# Potentiostat.net
KiCad netlist of a schematic drawn in EAGLE
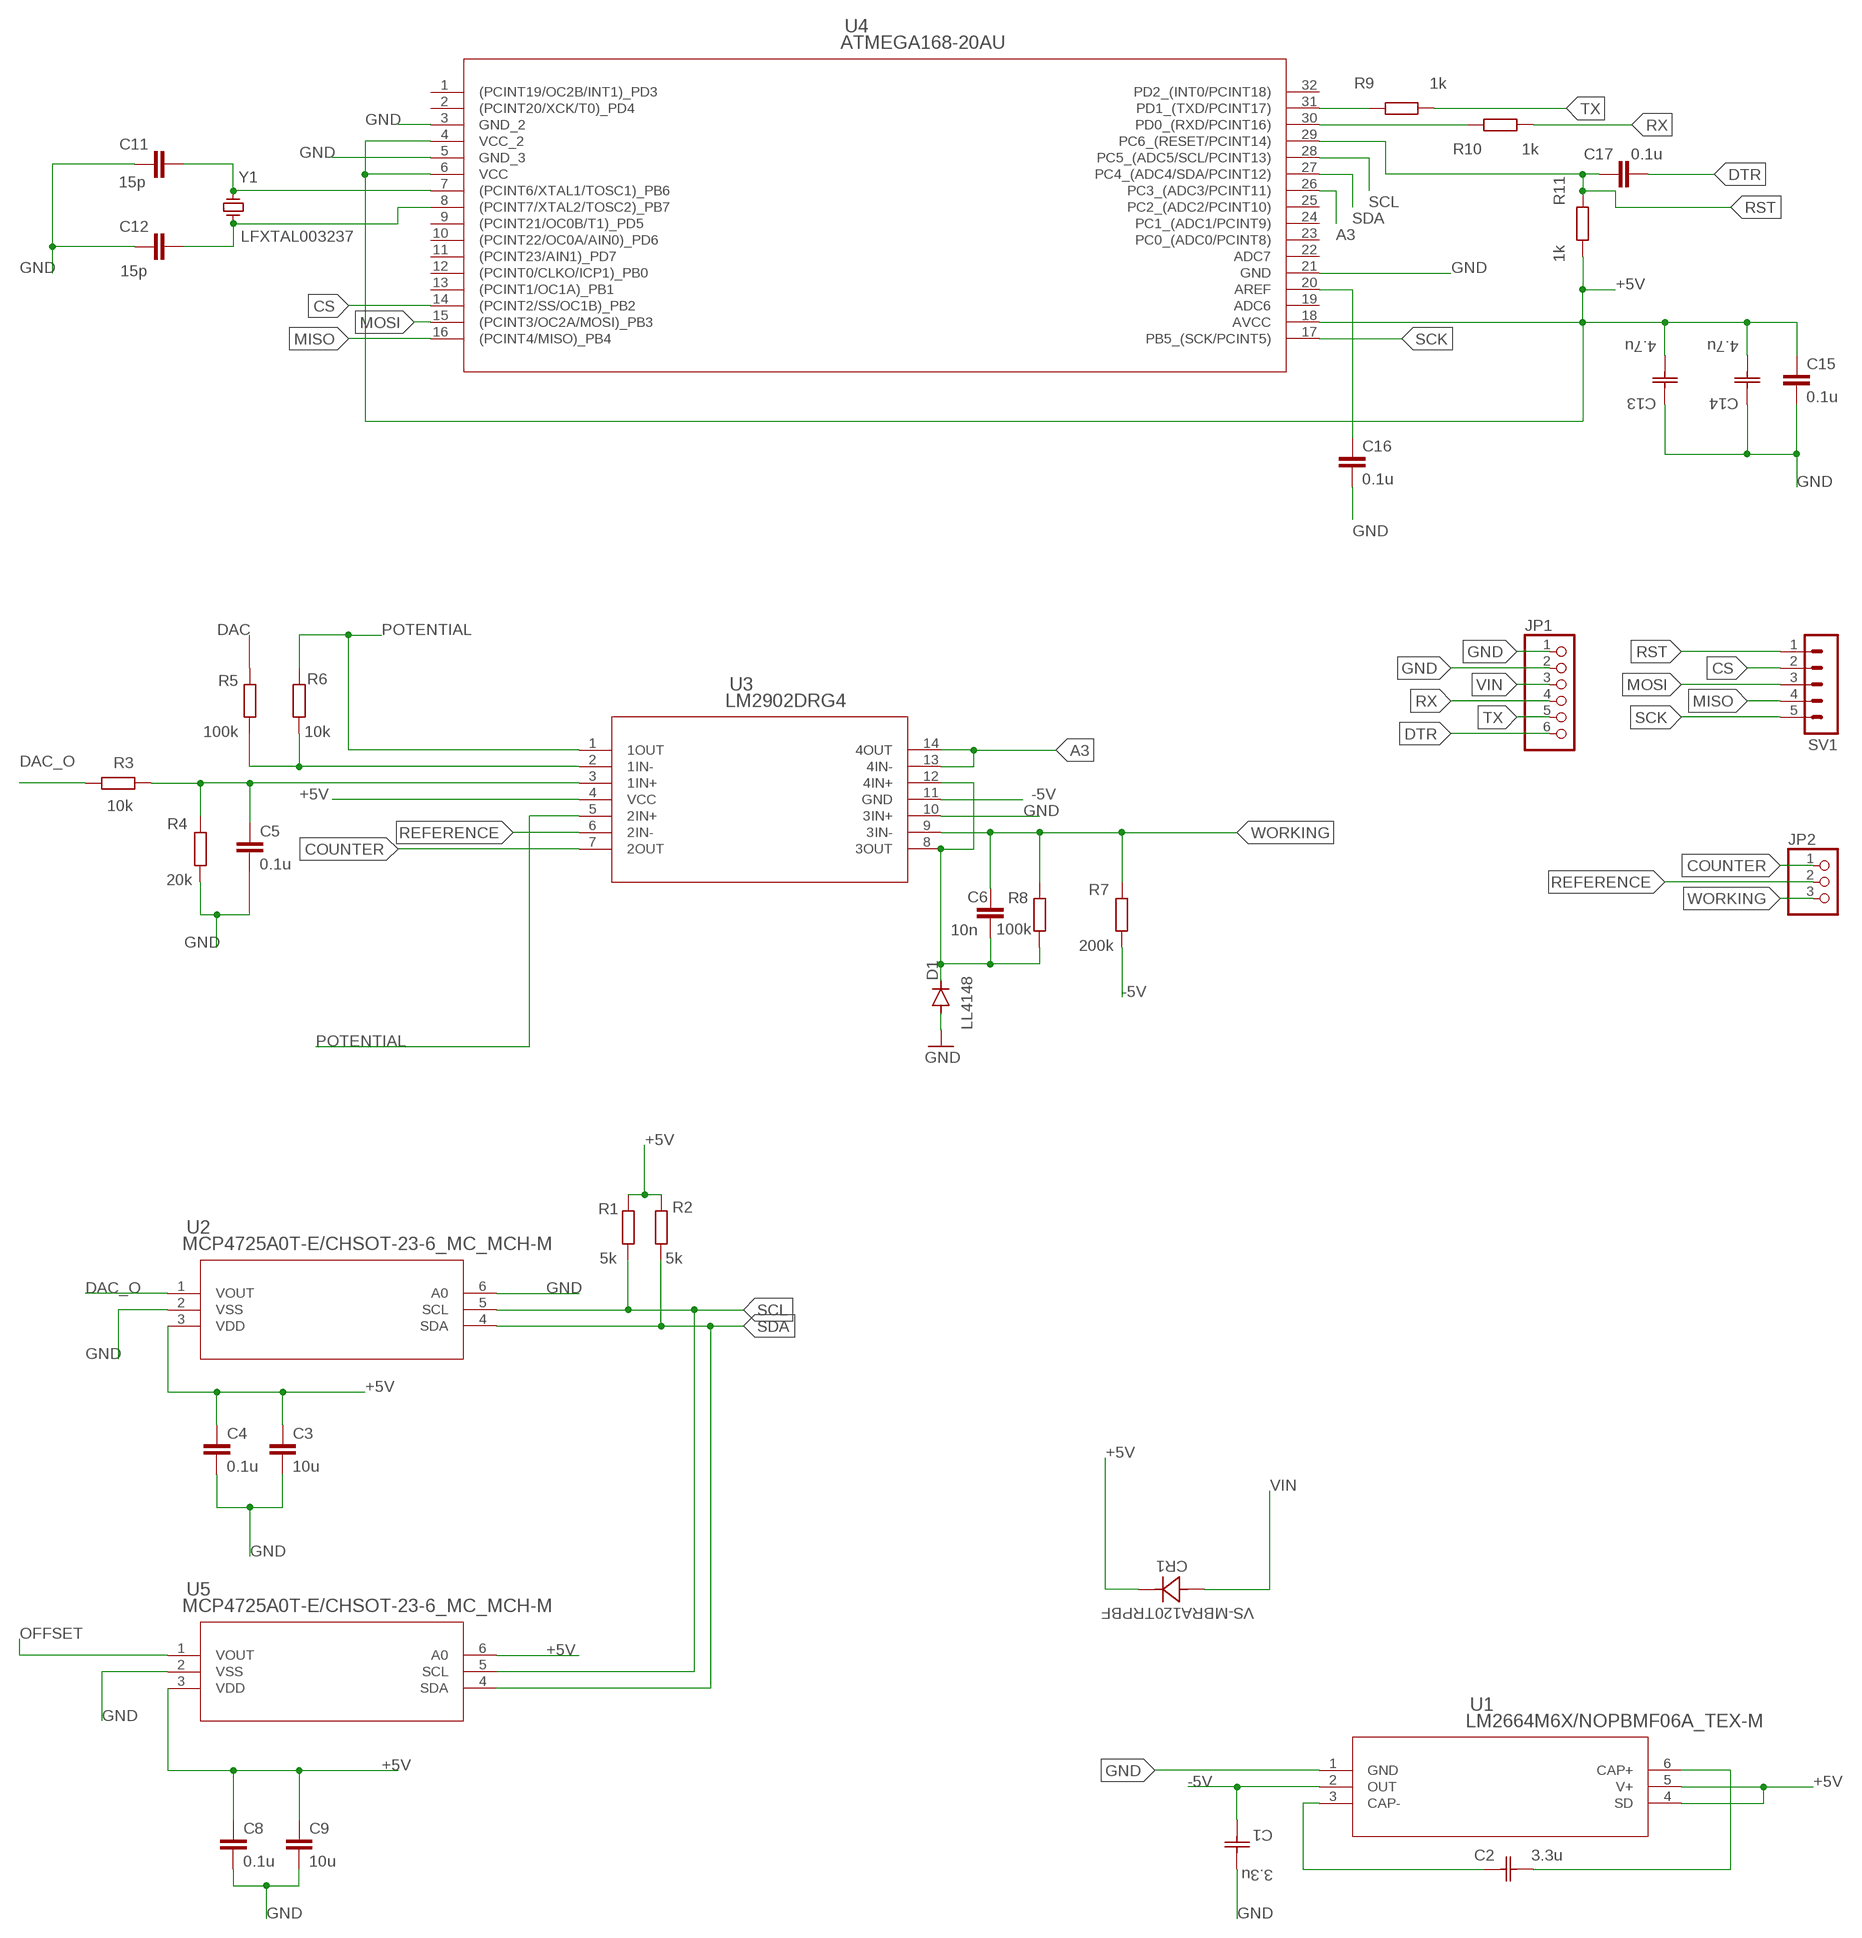
[diagram p0: schematic, sheet 1]

(export (version "E")
  (design (tool "Eeschema 10.0.6"))
  (components
    (comp (ref "C1")
      (value "3.3u")
      (footprint "eagle-import:CAP_293D_A_VIS-M")
      (fields (field (name "MANUFACTURER_PART_NUMBER") "293D335X9016A2TE3"))
      (libsource (lib "eagle-import") (part "293D335X9016A2TE3CAP_293D_A_VIS-M"))
    )
    (comp (ref "C2")
      (value "3.3u")
      (footprint "eagle-import:CAP_293D_A_VIS-M")
      (fields (field (name "MANUFACTURER_PART_NUMBER") "293D335X9016A2TE3"))
      (libsource (lib "eagle-import") (part "293D335X9016A2TE3CAP_293D_A_VIS-M"))
    )
    (comp (ref "C3")
      (value "10u")
      (footprint "eagle-import:C0805")
      (libsource (lib "eagle-import") (part "C-EUC0805"))
    )
    (comp (ref "C4")
      (value "0.1u")
      (footprint "eagle-import:C0805")
      (libsource (lib "eagle-import") (part "C-EUC0805"))
    )
    (comp (ref "C5")
      (value "0.1u")
      (footprint "eagle-import:C0805")
      (libsource (lib "eagle-import") (part "C-EUC0805"))
    )
    (comp (ref "C6")
      (value "10n")
      (footprint "eagle-import:C0805")
      (libsource (lib "eagle-import") (part "C-EUC0805"))
    )
    (comp (ref "C8")
      (value "0.1u")
      (footprint "eagle-import:C0805")
      (libsource (lib "eagle-import") (part "C-EUC0805"))
    )
    (comp (ref "C9")
      (value "10u")
      (footprint "eagle-import:C0805")
      (libsource (lib "eagle-import") (part "C-EUC0805"))
    )
    (comp (ref "C11")
      (value "15p")
      (footprint "eagle-import:C0805")
      (libsource (lib "eagle-import") (part "C-EUC0805"))
    )
    (comp (ref "C12")
      (value "15p")
      (footprint "eagle-import:C0805")
      (libsource (lib "eagle-import") (part "C-EUC0805"))
    )
    (comp (ref "C13")
      (value "4.7u")
      (footprint "eagle-import:CAP_293D_A_VIS-M")
      (fields (field (name "MANUFACTURER_PART_NUMBER") "293D335X9016A2TE3"))
      (libsource (lib "eagle-import") (part "293D335X9016A2TE3CAP_293D_A_VIS-M"))
    )
    (comp (ref "C14")
      (value "4.7u")
      (footprint "eagle-import:CAP_293D_A_VIS-M")
      (fields (field (name "MANUFACTURER_PART_NUMBER") "293D335X9016A2TE3"))
      (libsource (lib "eagle-import") (part "293D335X9016A2TE3CAP_293D_A_VIS-M"))
    )
    (comp (ref "C15")
      (value "0.1u")
      (footprint "eagle-import:C0805")
      (libsource (lib "eagle-import") (part "C-EUC0805"))
    )
    (comp (ref "C16")
      (value "0.1u")
      (footprint "eagle-import:C0805")
      (libsource (lib "eagle-import") (part "C-EUC0805"))
    )
    (comp (ref "C17")
      (value "0.1u")
      (footprint "eagle-import:C0805")
      (libsource (lib "eagle-import") (part "C-EUC0805"))
    )
    (comp (ref "CR1")
      (value "VS-MBRA120TRPBF")
      (footprint "eagle-import:DIODE_SMA_VIS")
      (libsource (lib "eagle-import") (part "VS-MBRA120TRPBF"))
    )
    (comp (ref "D1")
      (value "LL4148")
      (footprint "eagle-import:SOD80C")
      (libsource (lib "eagle-import") (part "DIODE-SOD80C"))
    )
    (comp (ref "JP1")
      (value "PINHD-1X6CB")
      (footprint "eagle-import:1X06-CLEANBIG")
      (libsource (lib "eagle-import") (part "PINHD-1X6CB"))
    )
    (comp (ref "JP2")
      (value "PINHD-1X3CB")
      (footprint "eagle-import:1X03-CLEANBIG")
      (libsource (lib "eagle-import") (part "PINHD-1X3CB"))
    )
    (comp (ref "R1")
      (value "5k")
      (footprint "eagle-import:R0805")
      (libsource (lib "eagle-import") (part "R-EU_R0805"))
    )
    (comp (ref "R2")
      (value "5k")
      (footprint "eagle-import:R0805")
      (libsource (lib "eagle-import") (part "R-EU_R0805"))
    )
    (comp (ref "R3")
      (value "10k")
      (footprint "eagle-import:R0805")
      (libsource (lib "eagle-import") (part "R-EU_R0805"))
    )
    (comp (ref "R4")
      (value "20k")
      (footprint "eagle-import:R0805")
      (libsource (lib "eagle-import") (part "R-EU_R0805"))
    )
    (comp (ref "R5")
      (value "100k")
      (footprint "eagle-import:R0805")
      (libsource (lib "eagle-import") (part "R-EU_R0805"))
    )
    (comp (ref "R6")
      (value "10k")
      (footprint "eagle-import:R0805")
      (libsource (lib "eagle-import") (part "R-EU_R0805"))
    )
    (comp (ref "R7")
      (value "200k")
      (footprint "eagle-import:R0805")
      (libsource (lib "eagle-import") (part "R-EU_R0805"))
    )
    (comp (ref "R8")
      (value "100k")
      (footprint "eagle-import:R0805")
      (libsource (lib "eagle-import") (part "R-EU_R0805"))
    )
    (comp (ref "R9")
      (value "1k")
      (footprint "eagle-import:R0805")
      (libsource (lib "eagle-import") (part "R-EU_R0805"))
    )
    (comp (ref "R10")
      (value "1k")
      (footprint "eagle-import:R0805")
      (libsource (lib "eagle-import") (part "R-EU_R0805"))
    )
    (comp (ref "R11")
      (value "1k")
      (footprint "eagle-import:R0805")
      (libsource (lib "eagle-import") (part "R-EU_R0805"))
    )
    (comp (ref "SV1")
      (value "MA05-1")
      (footprint "eagle-import:MA05-1")
      (libsource (lib "eagle-import") (part "MA05-1"))
    )
    (comp (ref "U1")
      (value "LM2664M6X/NOPBMF06A_TEX-M")
      (footprint "eagle-import:MF06A_TEX-M")
      (fields (field (name "MANUFACTURER_PART_NUMBER") "LM2664M6X/NOPB"))
      (libsource (lib "eagle-import") (part "LM2664M6X/NOPBMF06A_TEX-M"))
    )
    (comp (ref "U2")
      (value "MCP4725A0T-E/CHSOT-23-6_MC_MCH-M")
      (footprint "eagle-import:SOT-23-6_MC_MCH-M")
      (fields (field (name "MANUFACTURER_PART_NUMBER") "MCP4725A0T-E/CH"))
      (libsource (lib "eagle-import") (part "MCP4725A0T-E/CHSOT-23-6_MC_MCH-M"))
    )
    (comp (ref "U3")
      (value "LM2902DRG4")
      (footprint "eagle-import:D14_TEX")
      (fields (field (name "MANUFACTURER") "Texas Instruments"))
      (libsource (lib "eagle-import") (part "LM2902DRG4"))
    )
    (comp (ref "U4")
      (value "ATMEGA168-20AU")
      (footprint "eagle-import:32A_ATM")
      (fields (field (name "COPYRIGHT") "Copyright (C) 2015 Accelerated Designs. All rights reserved"))
      (libsource (lib "eagle-import") (part "ATMEGA168-20AU"))
    )
    (comp (ref "U5")
      (value "MCP4725A0T-E/CHSOT-23-6_MC_MCH-M")
      (footprint "eagle-import:SOT-23-6_MC_MCH-M")
      (fields (field (name "MANUFACTURER_PART_NUMBER") "MCP4725A0T-E/CH"))
      (libsource (lib "eagle-import") (part "MCP4725A0T-E/CHSOT-23-6_MC_MCH-M"))
    )
    (comp (ref "Y1")
      (value "LFXTAL003237")
      (footprint "eagle-import:XTAL1140X490X430N")
      (fields (field (name "MF") "IQD Frequency Products"))
      (libsource (lib "eagle-import") (part "LFXTAL003237"))
    )
  )
  (nets
    (net (code "1") (name "/+5V") (class "Default")
      (node (ref "C13") (pin "2") (pinfunction "2_2") (pintype "passive"))
      (node (ref "C14") (pin "2") (pinfunction "2_2") (pintype "passive"))
      (node (ref "C15") (pin "1") (pinfunction "1_1") (pintype "passive"))
      (node (ref "C3") (pin "1") (pinfunction "1_1") (pintype "passive"))
      (node (ref "C4") (pin "1") (pinfunction "1_1") (pintype "passive"))
      (node (ref "C8") (pin "1") (pinfunction "1_1") (pintype "passive"))
      (node (ref "C9") (pin "1") (pinfunction "1_1") (pintype "passive"))
      (node (ref "CR1") (pin "1") (pinfunction "1_1") (pintype "passive"))
      (node (ref "R1") (pin "2") (pinfunction "2_2") (pintype "passive"))
      (node (ref "R11") (pin "1") (pinfunction "1_1") (pintype "passive"))
      (node (ref "R2") (pin "2") (pinfunction "2_2") (pintype "passive"))
      (node (ref "U1") (pin "4") (pinfunction "SD_4") (pintype "passive"))
      (node (ref "U1") (pin "5") (pinfunction "V+_5") (pintype "input"))
      (node (ref "U2") (pin "3") (pinfunction "VDD_3") (pintype "passive"))
      (node (ref "U3") (pin "4") (pinfunction "VCC_4") (pintype "power_in"))
      (node (ref "U4") (pin "18") (pinfunction "AVCC_18") (pintype "power_in"))
      (node (ref "U4") (pin "4") (pinfunction "VCC_2_4") (pintype "power_in"))
      (node (ref "U4") (pin "6") (pinfunction "VCC_6") (pintype "power_in"))
      (node (ref "U5") (pin "3") (pinfunction "VDD_3") (pintype "passive"))
      (node (ref "U5") (pin "6") (pinfunction "A0_6") (pintype "passive"))
    )
    (net (code "2") (name "/-5V") (class "Default")
      (node (ref "C1") (pin "2") (pinfunction "2_2") (pintype "passive"))
      (node (ref "R7") (pin "1") (pinfunction "1_1") (pintype "passive"))
      (node (ref "U1") (pin "2") (pinfunction "OUT_2") (pintype "output"))
      (node (ref "U3") (pin "11") (pinfunction "GND_11") (pintype "power_in"))
    )
    (net (code "3") (name "/DAC") (class "Default")
      (node (ref "R5") (pin "2") (pinfunction "2_2") (pintype "passive"))
    )
    (net (code "4") (name "/DAC_O") (class "Default")
      (node (ref "R3") (pin "2") (pinfunction "2_2") (pintype "passive"))
      (node (ref "U2") (pin "1") (pinfunction "VOUT_1") (pintype "passive"))
    )
    (net (code "5") (name "/OFFSET") (class "Default")
      (node (ref "U5") (pin "1") (pinfunction "VOUT_1") (pintype "passive"))
    )
    (net (code "6") (name "/POTENTIAL") (class "Default")
      (node (ref "R6") (pin "2") (pinfunction "2_2") (pintype "passive"))
      (node (ref "U3") (pin "1") (pinfunction "1OUT_1") (pintype "output"))
      (node (ref "U3") (pin "5") (pinfunction "2IN+_5") (pintype "input"))
    )
    (net (code "7") (name "A3") (class "Default")
      (node (ref "U3") (pin "13") (pinfunction "4IN-_13") (pintype "input"))
      (node (ref "U3") (pin "14") (pinfunction "4OUT_14") (pintype "output"))
      (node (ref "U4") (pin "26") (pinfunction "PC3_(ADC3/PCINT11)_26") (pintype "bidirectional"))
    )
    (net (code "8") (name "COUNTER") (class "Default")
      (node (ref "JP2") (pin "1") (pinfunction "1_1") (pintype "passive"))
      (node (ref "U3") (pin "7") (pinfunction "2OUT_7") (pintype "output"))
    )
    (net (code "9") (name "CS") (class "Default")
      (node (ref "SV1") (pin "2") (pinfunction "2_2") (pintype "passive"))
      (node (ref "U4") (pin "14") (pinfunction "(PCINT2/SS/OC1B)_PB2_14") (pintype "bidirectional"))
    )
    (net (code "10") (name "DTR") (class "Default")
      (node (ref "C17") (pin "2") (pinfunction "2_2") (pintype "passive"))
      (node (ref "JP1") (pin "6") (pinfunction "6_6") (pintype "passive"))
    )
    (net (code "11") (name "GND") (class "Default")
      (node (ref "C1") (pin "1") (pinfunction "1_1") (pintype "passive"))
      (node (ref "C11") (pin "1") (pinfunction "1_1") (pintype "passive"))
      (node (ref "C12") (pin "1") (pinfunction "1_1") (pintype "passive"))
      (node (ref "C13") (pin "1") (pinfunction "1_1") (pintype "passive"))
      (node (ref "C14") (pin "1") (pinfunction "1_1") (pintype "passive"))
      (node (ref "C15") (pin "2") (pinfunction "2_2") (pintype "passive"))
      (node (ref "C16") (pin "2") (pinfunction "2_2") (pintype "passive"))
      (node (ref "C3") (pin "2") (pinfunction "2_2") (pintype "passive"))
      (node (ref "C4") (pin "2") (pinfunction "2_2") (pintype "passive"))
      (node (ref "C5") (pin "2") (pinfunction "2_2") (pintype "passive"))
      (node (ref "C8") (pin "2") (pinfunction "2_2") (pintype "passive"))
      (node (ref "C9") (pin "2") (pinfunction "2_2") (pintype "passive"))
      (node (ref "D1") (pin "A") (pinfunction "A_A") (pintype "passive"))
      (node (ref "JP1") (pin "1") (pinfunction "1_1") (pintype "passive"))
      (node (ref "JP1") (pin "2") (pinfunction "2_2") (pintype "passive"))
      (node (ref "R4") (pin "1") (pinfunction "1_1") (pintype "passive"))
      (node (ref "U1") (pin "1") (pinfunction "GND_1") (pintype "passive"))
      (node (ref "U2") (pin "2") (pinfunction "VSS_2") (pintype "passive"))
      (node (ref "U2") (pin "6") (pinfunction "A0_6") (pintype "passive"))
      (node (ref "U3") (pin "10") (pinfunction "3IN+_10") (pintype "input"))
      (node (ref "U4") (pin "21") (pinfunction "GND_21") (pintype "power_in"))
      (node (ref "U4") (pin "3") (pinfunction "GND_2_3") (pintype "power_in"))
      (node (ref "U4") (pin "5") (pinfunction "GND_3_5") (pintype "power_in"))
      (node (ref "U5") (pin "2") (pinfunction "VSS_2") (pintype "passive"))
    )
    (net (code "12") (name "MISO") (class "Default")
      (node (ref "SV1") (pin "4") (pinfunction "4_4") (pintype "passive"))
      (node (ref "U4") (pin "16") (pinfunction "(PCINT4/MISO)_PB4_16") (pintype "bidirectional"))
    )
    (net (code "13") (name "MOSI") (class "Default")
      (node (ref "SV1") (pin "3") (pinfunction "3_3") (pintype "passive"))
      (node (ref "U4") (pin "15") (pinfunction "(PCINT3/OC2A/MOSI)_PB3_15") (pintype "bidirectional"))
    )
    (net (code "14") (name "Net-(U1-CAP+)") (class "Default")
      (node (ref "C2") (pin "2") (pinfunction "2_2") (pintype "passive"))
      (node (ref "U1") (pin "6") (pinfunction "CAP+_6") (pintype "passive"))
    )
    (net (code "15") (name "Net-(U1-CAP-)") (class "Default")
      (node (ref "C2") (pin "1") (pinfunction "1_1") (pintype "passive"))
      (node (ref "U1") (pin "3") (pinfunction "CAP-_3") (pintype "passive"))
    )
    (net (code "16") (name "Net-(U3-1IN+)") (class "Default")
      (node (ref "C5") (pin "1") (pinfunction "1_1") (pintype "passive"))
      (node (ref "R3") (pin "1") (pinfunction "1_1") (pintype "passive"))
      (node (ref "R4") (pin "2") (pinfunction "2_2") (pintype "passive"))
      (node (ref "U3") (pin "3") (pinfunction "1IN+_3") (pintype "input"))
    )
    (net (code "17") (name "Net-(U3-1IN-)") (class "Default")
      (node (ref "R5") (pin "1") (pinfunction "1_1") (pintype "passive"))
      (node (ref "R6") (pin "1") (pinfunction "1_1") (pintype "passive"))
      (node (ref "U3") (pin "2") (pinfunction "1IN-_2") (pintype "input"))
    )
    (net (code "18") (name "Net-(U3-3OUT)") (class "Default")
      (node (ref "C6") (pin "2") (pinfunction "2_2") (pintype "passive"))
      (node (ref "D1") (pin "C") (pinfunction "C_C") (pintype "passive"))
      (node (ref "R8") (pin "1") (pinfunction "1_1") (pintype "passive"))
      (node (ref "U3") (pin "12") (pinfunction "4IN+_12") (pintype "input"))
      (node (ref "U3") (pin "8") (pinfunction "3OUT_8") (pintype "output"))
    )
    (net (code "19") (name "Net-(U4-(PCINT6{slash}XTAL1{slash}TOSC1)_PB6)") (class "Default")
      (node (ref "C11") (pin "2") (pinfunction "2_2") (pintype "passive"))
      (node (ref "U4") (pin "7") (pinfunction "(PCINT6/XTAL1/TOSC1)_PB6_7") (pintype "bidirectional"))
      (node (ref "Y1") (pin "2") (pinfunction "2_2") (pintype "passive"))
    )
    (net (code "20") (name "Net-(U4-(PCINT7{slash}XTAL2{slash}TOSC2)_PB7)") (class "Default")
      (node (ref "C12") (pin "2") (pinfunction "2_2") (pintype "passive"))
      (node (ref "U4") (pin "8") (pinfunction "(PCINT7/XTAL2/TOSC2)_PB7_8") (pintype "bidirectional"))
      (node (ref "Y1") (pin "1") (pinfunction "1_1") (pintype "passive"))
    )
    (net (code "21") (name "Net-(U4-AREF)") (class "Default")
      (node (ref "C16") (pin "1") (pinfunction "1_1") (pintype "passive"))
      (node (ref "U4") (pin "20") (pinfunction "AREF_20") (pintype "passive"))
    )
    (net (code "22") (name "Net-(U4-PD0_(RXD{slash}PCINT16))") (class "Default")
      (node (ref "R10") (pin "2") (pinfunction "2_2") (pintype "passive"))
      (node (ref "U4") (pin "30") (pinfunction "PD0_(RXD/PCINT16)_30") (pintype "bidirectional"))
    )
    (net (code "23") (name "Net-(U4-PD1_(TXD{slash}PCINT17))") (class "Default")
      (node (ref "R9") (pin "2") (pinfunction "2_2") (pintype "passive"))
      (node (ref "U4") (pin "31") (pinfunction "PD1_(TXD/PCINT17)_31") (pintype "bidirectional"))
    )
    (net (code "24") (name "REFERENCE") (class "Default")
      (node (ref "JP2") (pin "2") (pinfunction "2_2") (pintype "passive"))
      (node (ref "U3") (pin "6") (pinfunction "2IN-_6") (pintype "input"))
    )
    (net (code "25") (name "RST") (class "Default")
      (node (ref "C17") (pin "1") (pinfunction "1_1") (pintype "passive"))
      (node (ref "R11") (pin "2") (pinfunction "2_2") (pintype "passive"))
      (node (ref "SV1") (pin "1") (pinfunction "1_1") (pintype "passive"))
      (node (ref "U4") (pin "29") (pinfunction "PC6_(RESET/PCINT14)_29") (pintype "bidirectional"))
    )
    (net (code "26") (name "RX") (class "Default")
      (node (ref "JP1") (pin "4") (pinfunction "4_4") (pintype "passive"))
      (node (ref "R10") (pin "1") (pinfunction "1_1") (pintype "passive"))
    )
    (net (code "27") (name "SCK") (class "Default")
      (node (ref "SV1") (pin "5") (pinfunction "5_5") (pintype "passive"))
      (node (ref "U4") (pin "17") (pinfunction "PB5_(SCK/PCINT5)_17") (pintype "bidirectional"))
    )
    (net (code "28") (name "SCL") (class "Default")
      (node (ref "R1") (pin "1") (pinfunction "1_1") (pintype "passive"))
      (node (ref "U2") (pin "5") (pinfunction "SCL_5") (pintype "passive"))
      (node (ref "U4") (pin "28") (pinfunction "PC5_(ADC5/SCL/PCINT13)_28") (pintype "bidirectional"))
      (node (ref "U5") (pin "5") (pinfunction "SCL_5") (pintype "passive"))
    )
    (net (code "29") (name "SDA") (class "Default")
      (node (ref "R2") (pin "1") (pinfunction "1_1") (pintype "passive"))
      (node (ref "U2") (pin "4") (pinfunction "SDA_4") (pintype "passive"))
      (node (ref "U4") (pin "27") (pinfunction "PC4_(ADC4/SDA/PCINT12)_27") (pintype "bidirectional"))
      (node (ref "U5") (pin "4") (pinfunction "SDA_4") (pintype "passive"))
    )
    (net (code "30") (name "TX") (class "Default")
      (node (ref "JP1") (pin "5") (pinfunction "5_5") (pintype "passive"))
      (node (ref "R9") (pin "1") (pinfunction "1_1") (pintype "passive"))
    )
    (net (code "31") (name "VIN") (class "Default")
      (node (ref "CR1") (pin "2") (pinfunction "2_2") (pintype "passive"))
      (node (ref "JP1") (pin "3") (pinfunction "3_3") (pintype "passive"))
    )
    (net (code "32") (name "WORKING") (class "Default")
      (node (ref "C6") (pin "1") (pinfunction "1_1") (pintype "passive"))
      (node (ref "JP2") (pin "3") (pinfunction "3_3") (pintype "passive"))
      (node (ref "R7") (pin "2") (pinfunction "2_2") (pintype "passive"))
      (node (ref "R8") (pin "2") (pinfunction "2_2") (pintype "passive"))
      (node (ref "U3") (pin "9") (pinfunction "3IN-_9") (pintype "input"))
    )
    (net (code "33") (name "unconnected-(U4-(PCINT0{slash}CLKO{slash}ICP1)_PB0-Pad12)") (class "Default")
      (node (ref "U4") (pin "12") (pinfunction "(PCINT0/CLKO/ICP1)_PB0_12") (pintype "bidirectional"))
    )
    (net (code "34") (name "unconnected-(U4-(PCINT1{slash}OC1A)_PB1-Pad13)") (class "Default")
      (node (ref "U4") (pin "13") (pinfunction "(PCINT1/OC1A)_PB1_13") (pintype "bidirectional"))
    )
    (net (code "35") (name "unconnected-(U4-(PCINT19{slash}OC2B{slash}INT1)_PD3-Pad1)") (class "Default")
      (node (ref "U4") (pin "1") (pinfunction "(PCINT19/OC2B/INT1)_PD3_1") (pintype "bidirectional"))
    )
    (net (code "36") (name "unconnected-(U4-(PCINT20{slash}XCK{slash}T0)_PD4-Pad2)") (class "Default")
      (node (ref "U4") (pin "2") (pinfunction "(PCINT20/XCK/T0)_PD4_2") (pintype "bidirectional"))
    )
    (net (code "37") (name "unconnected-(U4-(PCINT21{slash}OC0B{slash}T1)_PD5-Pad9)") (class "Default")
      (node (ref "U4") (pin "9") (pinfunction "(PCINT21/OC0B/T1)_PD5_9") (pintype "bidirectional"))
    )
    (net (code "38") (name "unconnected-(U4-(PCINT22{slash}OC0A{slash}AIN0)_PD6-Pad10)") (class "Default")
      (node (ref "U4") (pin "10") (pinfunction "(PCINT22/OC0A/AIN0)_PD6_10") (pintype "bidirectional"))
    )
    (net (code "39") (name "unconnected-(U4-(PCINT23{slash}AIN1)_PD7-Pad11)") (class "Default")
      (node (ref "U4") (pin "11") (pinfunction "(PCINT23/AIN1)_PD7_11") (pintype "bidirectional"))
    )
    (net (code "40") (name "unconnected-(U4-ADC6-Pad19)") (class "Default")
      (node (ref "U4") (pin "19") (pinfunction "ADC6_19") (pintype "input"))
    )
    (net (code "41") (name "unconnected-(U4-ADC7-Pad22)") (class "Default")
      (node (ref "U4") (pin "22") (pinfunction "ADC7_22") (pintype "input"))
    )
    (net (code "42") (name "unconnected-(U4-PC0_(ADC0{slash}PCINT8)-Pad23)") (class "Default")
      (node (ref "U4") (pin "23") (pinfunction "PC0_(ADC0/PCINT8)_23") (pintype "bidirectional"))
    )
    (net (code "43") (name "unconnected-(U4-PC1_(ADC1{slash}PCINT9)-Pad24)") (class "Default")
      (node (ref "U4") (pin "24") (pinfunction "PC1_(ADC1/PCINT9)_24") (pintype "bidirectional"))
    )
    (net (code "44") (name "unconnected-(U4-PC2_(ADC2{slash}PCINT10)-Pad25)") (class "Default")
      (node (ref "U4") (pin "25") (pinfunction "PC2_(ADC2/PCINT10)_25") (pintype "bidirectional"))
    )
    (net (code "45") (name "unconnected-(U4-PD2_(INT0{slash}PCINT18)-Pad32)") (class "Default")
      (node (ref "U4") (pin "32") (pinfunction "PD2_(INT0/PCINT18)_32") (pintype "bidirectional"))
    )
  )
)
